# EMG_FSR.net
KiCad netlist of a schematic drawn in EAGLE
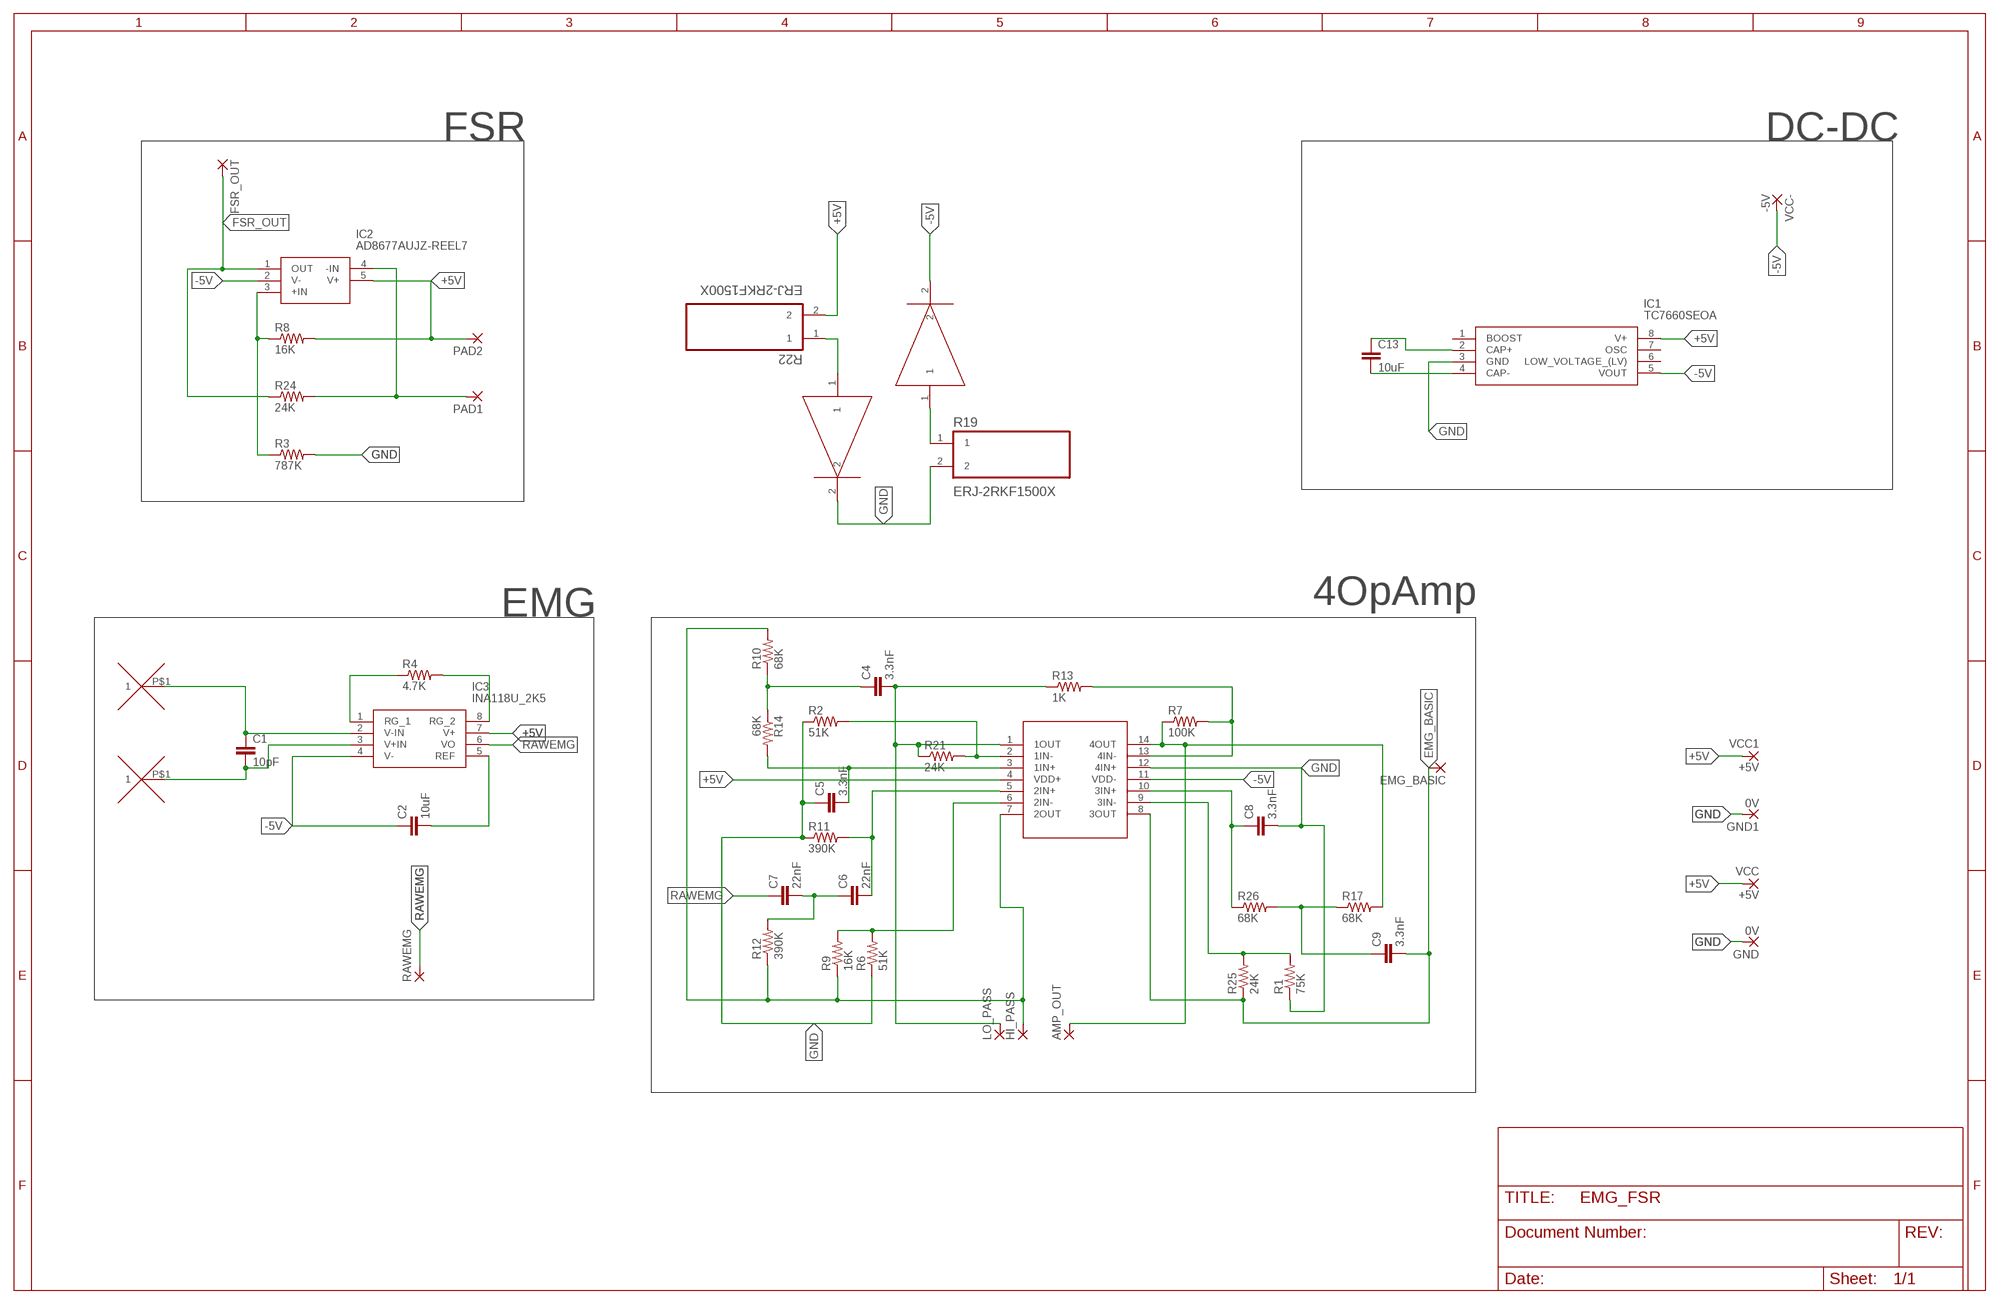
[diagram p0: schematic, sheet 1]

(export (version "E")
  (design (tool "Eeschema 10.0.6"))
  (components
    (comp (ref "AMP_OUT")
      (value "1,6/0,8")
      (footprint "eagle-import:1,6_0,8")
      (libsource (lib "eagle-import") (part "1,6/0,8"))
    )
    (comp (ref "BLUE")
      (value "RESC0402X40N")
      (footprint "eagle-import:RESC0402X40N")
      (fields (field (name "MANUFACTURER") "KOA"))
      (libsource (lib "eagle-import") (part "RESC0402X40N"))
    )
    (comp (ref "C1")
      (value "10pF")
      (footprint "eagle-import:HPC0201")
      (libsource (lib "eagle-import") (part "rcl@1_C-EUHPC0201"))
    )
    (comp (ref "C2")
      (value "10uF")
      (footprint "eagle-import:C0805")
      (libsource (lib "eagle-import") (part "rcl@1_C-EUC0805"))
    )
    (comp (ref "C4")
      (value "3.3nF")
      (footprint "eagle-import:C1206")
      (libsource (lib "eagle-import") (part "C-EUC1206"))
    )
    (comp (ref "C5")
      (value "3.3nF")
      (footprint "eagle-import:C1206")
      (libsource (lib "eagle-import") (part "C-EUC1206"))
    )
    (comp (ref "C6")
      (value "22nF")
      (footprint "eagle-import:C0805")
      (libsource (lib "eagle-import") (part "C-EUC0805"))
    )
    (comp (ref "C7")
      (value "22nF")
      (footprint "eagle-import:C0805")
      (libsource (lib "eagle-import") (part "C-EUC0805"))
    )
    (comp (ref "C8")
      (value "3.3nF")
      (footprint "eagle-import:C1206")
      (libsource (lib "eagle-import") (part "C-EUC1206"))
    )
    (comp (ref "C9")
      (value "3.3nF")
      (footprint "eagle-import:C1206")
      (libsource (lib "eagle-import") (part "C-EUC1206"))
    )
    (comp (ref "C13")
      (value "10uF")
      (footprint "eagle-import:C0805K")
      (libsource (lib "eagle-import") (part "rcl@1_C-EUC0805K"))
    )
    (comp (ref "EMG_BASIC")
      (value "1,6/0,8")
      (footprint "eagle-import:1,6_0,8")
      (libsource (lib "eagle-import") (part "1,6/0,8"))
    )
    (comp (ref "FSR_OUT")
      (value "1,6/0,8")
      (footprint "eagle-import:1,6_0,8")
      (libsource (lib "eagle-import") (part "1,6/0,8"))
    )
    (comp (ref "GND")
      (value "0V")
      (footprint "eagle-import:1,6_0,8")
      (libsource (lib "eagle-import") (part "1,6/0,8"))
    )
    (comp (ref "GND1")
      (value "0V")
      (footprint "eagle-import:1,6_0,8")
      (libsource (lib "eagle-import") (part "1,6/0,8"))
    )
    (comp (ref "HI_PASS")
      (value "1,6/0,8")
      (footprint "eagle-import:1,6_0,8")
      (libsource (lib "eagle-import") (part "1,6/0,8"))
    )
    (comp (ref "IC1")
      (value "TC7660SEOA")
      (footprint "eagle-import:SOIC127P600X175-8N")
      (fields (field (name "MOUSER_PART_NUMBER") "579-TC7660SEOA"))
      (libsource (lib "eagle-import") (part "TC7660SEOA"))
    )
    (comp (ref "IC2")
      (value "AD8677AUJZ-REEL7")
      (footprint "eagle-import:SOT95P280X100-5N")
      (fields (field (name "MOUSER_PART_NUMBER") "584-AD8677AUJZ-R7"))
      (libsource (lib "eagle-import") (part "AD8677AUJZ-REEL7"))
    )
    (comp (ref "IC3")
      (value "INA118U_2K5")
      (footprint "eagle-import:SOIC127P600X175-8N")
      (fields
        (field (name "ARROW_PART_NUMBER") "INA118U/2K5")
        (field (name "MOUSER_PART_NUMBER") "595-INA118U/2K5")
      )
      (libsource (lib "eagle-import") (part "INA118U_2K5"))
    )
    (comp (ref "LO_PASS")
      (value "1,6/0,8")
      (footprint "eagle-import:1,6_0,8")
      (libsource (lib "eagle-import") (part "1,6/0,8"))
    )
    (comp (ref "PAD1")
      (value "SMD2")
      (footprint "eagle-import:SMD1,27-2,54")
      (libsource (lib "eagle-import") (part "SMD2"))
    )
    (comp (ref "PAD2")
      (value "SMD2")
      (footprint "eagle-import:SMD1,27-2,54")
      (libsource (lib "eagle-import") (part "SMD2"))
    )
    (comp (ref "R1")
      (value "75K")
      (footprint "eagle-import:R0402")
      (libsource (lib "eagle-import") (part "adafruit@2_R-US_R0402"))
    )
    (comp (ref "R2")
      (value "51K")
      (footprint "eagle-import:R0402")
      (libsource (lib "eagle-import") (part "adafruit@2_R-US_R0402"))
    )
    (comp (ref "R3")
      (value "787K")
      (footprint "eagle-import:R0805")
      (libsource (lib "eagle-import") (part "rcl_R-US_R0805"))
    )
    (comp (ref "R4")
      (value "4.7K")
      (footprint "eagle-import:R0402")
      (libsource (lib "eagle-import") (part "adafruit@1_R-US_R0402"))
    )
    (comp (ref "R6")
      (value "51K")
      (footprint "eagle-import:R0402")
      (libsource (lib "eagle-import") (part "adafruit@2_R-US_R0402"))
    )
    (comp (ref "R7")
      (value "100K")
      (footprint "eagle-import:R1005")
      (libsource (lib "eagle-import") (part "adafruit@1_R-US_R1005"))
    )
    (comp (ref "R8")
      (value "16K")
      (footprint "eagle-import:R0402")
      (libsource (lib "eagle-import") (part "adafruit@2_R-US_R0402"))
    )
    (comp (ref "R9")
      (value "16K")
      (footprint "eagle-import:R0402")
      (libsource (lib "eagle-import") (part "adafruit@2_R-US_R0402"))
    )
    (comp (ref "R10")
      (value "68K")
      (footprint "eagle-import:R0402")
      (libsource (lib "eagle-import") (part "adafruit@2_R-US_R0402"))
    )
    (comp (ref "R11")
      (value "390K")
      (footprint "eagle-import:R0603")
      (libsource (lib "eagle-import") (part "R-US_R0603"))
    )
    (comp (ref "R12")
      (value "390K")
      (footprint "eagle-import:R0603")
      (libsource (lib "eagle-import") (part "adafruit@1_R-US_R0603"))
    )
    (comp (ref "R13")
      (value "1K")
      (footprint "eagle-import:R0402")
      (libsource (lib "eagle-import") (part "adafruit@2_R-US_R0402"))
    )
    (comp (ref "R14")
      (value "68K")
      (footprint "eagle-import:R0402")
      (libsource (lib "eagle-import") (part "adafruit@2_R-US_R0402"))
    )
    (comp (ref "R17")
      (value "68K")
      (footprint "eagle-import:R0402")
      (libsource (lib "eagle-import") (part "adafruit@2_R-US_R0402"))
    )
    (comp (ref "R19")
      (value "ERJ-2RKF1500X")
      (footprint "eagle-import:RESC1005X40N")
      (fields (field (name "DIGI-KEY_PART_NUMBER") "P150LCT-ND") (field (name "MF") "Panasonic Electronic"))
      (libsource (lib "eagle-import") (part "ERJ-2RKF1500X"))
    )
    (comp (ref "R21")
      (value "24K")
      (footprint "eagle-import:R0402")
      (libsource (lib "eagle-import") (part "adafruit@2_R-US_R0402"))
    )
    (comp (ref "R22")
      (value "ERJ-2RKF1500X")
      (footprint "eagle-import:RESC1005X40N")
      (fields (field (name "DIGI-KEY_PART_NUMBER") "P150LCT-ND") (field (name "MF") "Panasonic Electronic"))
      (libsource (lib "eagle-import") (part "ERJ-2RKF1500X"))
    )
    (comp (ref "R24")
      (value "24K")
      (footprint "eagle-import:R0402")
      (libsource (lib "eagle-import") (part "adafruit@2_R-US_R0402"))
    )
    (comp (ref "R25")
      (value "24K")
      (footprint "eagle-import:R0402")
      (libsource (lib "eagle-import") (part "adafruit@2_R-US_R0402"))
    )
    (comp (ref "R26")
      (value "68K")
      (footprint "eagle-import:R0402")
      (libsource (lib "eagle-import") (part "adafruit@2_R-US_R0402"))
    )
    (comp (ref "RAWEMG")
      (value "1,6/0,8")
      (footprint "eagle-import:1,6_0,8")
      (libsource (lib "eagle-import") (part "1,6/0,8"))
    )
    (comp (ref "RED")
      (value "RESC0402X40N")
      (footprint "eagle-import:RESC0402X40N")
      (fields (field (name "MANUFACTURER") "KOA"))
      (libsource (lib "eagle-import") (part "RESC0402X40N"))
    )
    (comp (ref "U$1")
      (value "TLC2274-HT")
      (footprint "eagle-import:SOP65P640X120-14N")
      (libsource (lib "eagle-import") (part "TLC2274-HT"))
    )
    (comp (ref "U$2")
      (value "EMG_VIA")
      (footprint "eagle-import:EMG_VIA")
      (libsource (lib "eagle-import") (part "EMG_VIA"))
    )
    (comp (ref "U$3")
      (value "EMG_VIA")
      (footprint "eagle-import:EMG_VIA")
      (libsource (lib "eagle-import") (part "EMG_VIA"))
    )
    (comp (ref "VCC")
      (value "+5V")
      (footprint "eagle-import:1,6_0,8")
      (libsource (lib "eagle-import") (part "1,6/0,8"))
    )
    (comp (ref "VCC-")
      (value "-5V")
      (footprint "eagle-import:1,6_0,8")
      (libsource (lib "eagle-import") (part "1,6/0,8"))
    )
    (comp (ref "VCC1")
      (value "+5V")
      (footprint "eagle-import:1,6_0,8")
      (libsource (lib "eagle-import") (part "1,6/0,8"))
    )
  )
  (nets
    (net (code "1") (name "+5V") (class "Default")
      (node (ref "IC1") (pin "8") (pinfunction "V+_8") (pintype "bidirectional"))
      (node (ref "IC2") (pin "5") (pinfunction "V+_5") (pintype "bidirectional"))
      (node (ref "IC3") (pin "7") (pinfunction "V+_7") (pintype "bidirectional"))
      (node (ref "PAD2") (pin "1") (pinfunction "P_1") (pintype "passive"))
      (node (ref "R22") (pin "2") (pinfunction "2_2") (pintype "bidirectional"))
      (node (ref "R8") (pin "2") (pinfunction "2_2") (pintype "passive"))
      (node (ref "U$1") (pin "4") (pinfunction "VDD+_4") (pintype "bidirectional"))
      (node (ref "VCC") (pin "1") (pinfunction "P_1") (pintype "passive"))
      (node (ref "VCC1") (pin "1") (pinfunction "P_1") (pintype "passive"))
    )
    (net (code "2") (name "-5V") (class "Default")
      (node (ref "BLUE") (pin "2") (pinfunction "2_2") (pintype "bidirectional"))
      (node (ref "C2") (pin "1") (pinfunction "1_1") (pintype "passive"))
      (node (ref "IC1") (pin "5") (pinfunction "VOUT_5") (pintype "bidirectional"))
      (node (ref "IC2") (pin "2") (pinfunction "V-_2") (pintype "bidirectional"))
      (node (ref "IC3") (pin "4") (pinfunction "V-_4") (pintype "bidirectional"))
      (node (ref "U$1") (pin "11") (pinfunction "VDD-_11") (pintype "bidirectional"))
      (node (ref "VCC-") (pin "1") (pinfunction "P_1") (pintype "passive"))
    )
    (net (code "3") (name "EMG_BASIC") (class "Default")
      (node (ref "C9") (pin "2") (pinfunction "2_2") (pintype "passive"))
      (node (ref "EMG_BASIC") (pin "1") (pinfunction "P_1") (pintype "passive"))
      (node (ref "R25") (pin "1") (pinfunction "1_1") (pintype "passive"))
      (node (ref "U$1") (pin "8") (pinfunction "3OUT_8") (pintype "bidirectional"))
    )
    (net (code "4") (name "FSR_OUT") (class "Default")
      (node (ref "FSR_OUT") (pin "1") (pinfunction "P_1") (pintype "passive"))
      (node (ref "IC2") (pin "1") (pinfunction "OUT_1") (pintype "output"))
      (node (ref "R24") (pin "1") (pinfunction "1_1") (pintype "passive"))
    )
    (net (code "5") (name "GND") (class "Default")
      (node (ref "C5") (pin "1") (pinfunction "1_1") (pintype "passive"))
      (node (ref "C8") (pin "2") (pinfunction "2_2") (pintype "passive"))
      (node (ref "GND") (pin "1") (pinfunction "P_1") (pintype "passive"))
      (node (ref "GND1") (pin "1") (pinfunction "P_1") (pintype "passive"))
      (node (ref "IC1") (pin "3") (pinfunction "GND_3") (pintype "bidirectional"))
      (node (ref "R1") (pin "1") (pinfunction "1_1") (pintype "passive"))
      (node (ref "R11") (pin "1") (pinfunction "1_1") (pintype "passive"))
      (node (ref "R19") (pin "2") (pinfunction "2_2") (pintype "bidirectional"))
      (node (ref "R2") (pin "1") (pinfunction "1_1") (pintype "passive"))
      (node (ref "R3") (pin "2") (pinfunction "2_2") (pintype "passive"))
      (node (ref "R6") (pin "1") (pinfunction "1_1") (pintype "passive"))
      (node (ref "RED") (pin "2") (pinfunction "2_2") (pintype "bidirectional"))
      (node (ref "U$1") (pin "12") (pinfunction "4IN+_12") (pintype "bidirectional"))
    )
    (net (code "6") (name "Net-(AMP_OUT-P)") (class "Default")
      (node (ref "AMP_OUT") (pin "1") (pinfunction "P_1") (pintype "passive"))
      (node (ref "R17") (pin "2") (pinfunction "2_2") (pintype "passive"))
      (node (ref "R7") (pin "1") (pinfunction "1_1") (pintype "passive"))
      (node (ref "U$1") (pin "14") (pinfunction "4OUT_14") (pintype "bidirectional"))
    )
    (net (code "7") (name "Net-(BLUE-Pad1)") (class "Default")
      (node (ref "BLUE") (pin "1") (pinfunction "1_1") (pintype "bidirectional"))
      (node (ref "R19") (pin "1") (pinfunction "1_1") (pintype "bidirectional"))
    )
    (net (code "8") (name "Net-(C4-Pad1)") (class "Default")
      (node (ref "C4") (pin "1") (pinfunction "1_1") (pintype "passive"))
      (node (ref "R10") (pin "1") (pinfunction "1_1") (pintype "passive"))
      (node (ref "R14") (pin "1") (pinfunction "1_1") (pintype "passive"))
    )
    (net (code "9") (name "Net-(C6-Pad1)") (class "Default")
      (node (ref "C6") (pin "1") (pinfunction "1_1") (pintype "passive"))
      (node (ref "C7") (pin "2") (pinfunction "2_2") (pintype "passive"))
      (node (ref "R12") (pin "2") (pinfunction "2_2") (pintype "passive"))
    )
    (net (code "10") (name "Net-(C9-Pad1)") (class "Default")
      (node (ref "C9") (pin "1") (pinfunction "1_1") (pintype "passive"))
      (node (ref "R17") (pin "1") (pinfunction "1_1") (pintype "passive"))
      (node (ref "R26") (pin "2") (pinfunction "2_2") (pintype "passive"))
    )
    (net (code "11") (name "Net-(HI_PASS-P)") (class "Default")
      (node (ref "HI_PASS") (pin "1") (pinfunction "P_1") (pintype "passive"))
      (node (ref "R10") (pin "2") (pinfunction "2_2") (pintype "passive"))
      (node (ref "R12") (pin "1") (pinfunction "1_1") (pintype "passive"))
      (node (ref "R9") (pin "1") (pinfunction "1_1") (pintype "passive"))
      (node (ref "U$1") (pin "7") (pinfunction "2OUT_7") (pintype "bidirectional"))
    )
    (net (code "12") (name "Net-(IC1-CAP+)") (class "Default")
      (node (ref "C13") (pin "1") (pinfunction "1_1") (pintype "passive"))
      (node (ref "IC1") (pin "2") (pinfunction "CAP+_2") (pintype "bidirectional"))
    )
    (net (code "13") (name "Net-(IC1-CAP-)") (class "Default")
      (node (ref "C13") (pin "2") (pinfunction "2_2") (pintype "passive"))
      (node (ref "IC1") (pin "4") (pinfunction "CAP-_4") (pintype "bidirectional"))
    )
    (net (code "14") (name "Net-(IC2-+IN)") (class "Default")
      (node (ref "IC2") (pin "3") (pinfunction "+IN_3") (pintype "input"))
      (node (ref "R3") (pin "1") (pinfunction "1_1") (pintype "passive"))
      (node (ref "R8") (pin "1") (pinfunction "1_1") (pintype "passive"))
    )
    (net (code "15") (name "Net-(IC2--IN)") (class "Default")
      (node (ref "IC2") (pin "4") (pinfunction "-IN_4") (pintype "input"))
      (node (ref "PAD1") (pin "1") (pinfunction "P_1") (pintype "passive"))
      (node (ref "R24") (pin "2") (pinfunction "2_2") (pintype "passive"))
    )
    (net (code "16") (name "Net-(IC3-REF)") (class "Default")
      (node (ref "C2") (pin "2") (pinfunction "2_2") (pintype "passive"))
      (node (ref "IC3") (pin "5") (pinfunction "REF_5") (pintype "bidirectional"))
    )
    (net (code "17") (name "Net-(IC3-RG_1)") (class "Default")
      (node (ref "IC3") (pin "1") (pinfunction "RG_1_1") (pintype "bidirectional"))
      (node (ref "R4") (pin "1") (pinfunction "1_1") (pintype "passive"))
    )
    (net (code "18") (name "Net-(IC3-RG_2)") (class "Default")
      (node (ref "IC3") (pin "8") (pinfunction "RG_2_8") (pintype "bidirectional"))
      (node (ref "R4") (pin "2") (pinfunction "2_2") (pintype "passive"))
    )
    (net (code "19") (name "Net-(IC3-V+IN)") (class "Default")
      (node (ref "C1") (pin "2") (pinfunction "2_2") (pintype "passive"))
      (node (ref "IC3") (pin "3") (pinfunction "V+IN_3") (pintype "bidirectional"))
      (node (ref "U$3") (pin "P$1") (pinfunction "1_P$1") (pintype "bidirectional"))
    )
    (net (code "20") (name "Net-(IC3-V-IN)") (class "Default")
      (node (ref "C1") (pin "1") (pinfunction "1_1") (pintype "passive"))
      (node (ref "IC3") (pin "2") (pinfunction "V-IN_2") (pintype "bidirectional"))
      (node (ref "U$2") (pin "P$1") (pinfunction "1_P$1") (pintype "bidirectional"))
    )
    (net (code "21") (name "Net-(LO_PASS-P)") (class "Default")
      (node (ref "C4") (pin "2") (pinfunction "2_2") (pintype "passive"))
      (node (ref "LO_PASS") (pin "1") (pinfunction "P_1") (pintype "passive"))
      (node (ref "R13") (pin "1") (pinfunction "1_1") (pintype "passive"))
      (node (ref "R21") (pin "1") (pinfunction "1_1") (pintype "passive"))
      (node (ref "U$1") (pin "1") (pinfunction "1OUT_1") (pintype "bidirectional"))
    )
    (net (code "22") (name "Net-(R22-Pad1)") (class "Default")
      (node (ref "R22") (pin "1") (pinfunction "1_1") (pintype "bidirectional"))
      (node (ref "RED") (pin "1") (pinfunction "1_1") (pintype "bidirectional"))
    )
    (net (code "23") (name "Net-(U$1-1IN+)") (class "Default")
      (node (ref "C5") (pin "2") (pinfunction "2_2") (pintype "passive"))
      (node (ref "R14") (pin "2") (pinfunction "2_2") (pintype "passive"))
      (node (ref "U$1") (pin "3") (pinfunction "1IN+_3") (pintype "bidirectional"))
    )
    (net (code "24") (name "Net-(U$1-1IN-)") (class "Default")
      (node (ref "R2") (pin "2") (pinfunction "2_2") (pintype "passive"))
      (node (ref "R21") (pin "2") (pinfunction "2_2") (pintype "passive"))
      (node (ref "U$1") (pin "2") (pinfunction "1IN-_2") (pintype "bidirectional"))
    )
    (net (code "25") (name "Net-(U$1-2IN+)") (class "Default")
      (node (ref "C6") (pin "2") (pinfunction "2_2") (pintype "passive"))
      (node (ref "R11") (pin "2") (pinfunction "2_2") (pintype "passive"))
      (node (ref "U$1") (pin "5") (pinfunction "2IN+_5") (pintype "bidirectional"))
    )
    (net (code "26") (name "Net-(U$1-2IN-)") (class "Default")
      (node (ref "R6") (pin "2") (pinfunction "2_2") (pintype "passive"))
      (node (ref "R9") (pin "2") (pinfunction "2_2") (pintype "passive"))
      (node (ref "U$1") (pin "6") (pinfunction "2IN-_6") (pintype "bidirectional"))
    )
    (net (code "27") (name "Net-(U$1-3IN+)") (class "Default")
      (node (ref "C8") (pin "1") (pinfunction "1_1") (pintype "passive"))
      (node (ref "R26") (pin "1") (pinfunction "1_1") (pintype "passive"))
      (node (ref "U$1") (pin "10") (pinfunction "3IN+_10") (pintype "bidirectional"))
    )
    (net (code "28") (name "Net-(U$1-3IN-)") (class "Default")
      (node (ref "R1") (pin "2") (pinfunction "2_2") (pintype "passive"))
      (node (ref "R25") (pin "2") (pinfunction "2_2") (pintype "passive"))
      (node (ref "U$1") (pin "9") (pinfunction "3IN-_9") (pintype "bidirectional"))
    )
    (net (code "29") (name "Net-(U$1-4IN-)") (class "Default")
      (node (ref "R13") (pin "2") (pinfunction "2_2") (pintype "passive"))
      (node (ref "R7") (pin "2") (pinfunction "2_2") (pintype "passive"))
      (node (ref "U$1") (pin "13") (pinfunction "4IN-_13") (pintype "bidirectional"))
    )
    (net (code "30") (name "RAWEMG") (class "Default")
      (node (ref "C7") (pin "1") (pinfunction "1_1") (pintype "passive"))
      (node (ref "IC3") (pin "6") (pinfunction "VO_6") (pintype "bidirectional"))
      (node (ref "RAWEMG") (pin "1") (pinfunction "P_1") (pintype "passive"))
    )
    (net (code "31") (name "unconnected-(IC1-BOOST-Pad1)") (class "Default")
      (node (ref "IC1") (pin "1") (pinfunction "BOOST_1") (pintype "bidirectional"))
    )
    (net (code "32") (name "unconnected-(IC1-LOW_VOLTAGE_(LV)-Pad6)") (class "Default")
      (node (ref "IC1") (pin "6") (pinfunction "LOW_VOLTAGE_(LV)_6") (pintype "bidirectional"))
    )
    (net (code "33") (name "unconnected-(IC1-OSC-Pad7)") (class "Default")
      (node (ref "IC1") (pin "7") (pinfunction "OSC_7") (pintype "bidirectional"))
    )
  )
)
